# IO.net
KiCad netlist of a schematic drawn in EAGLE
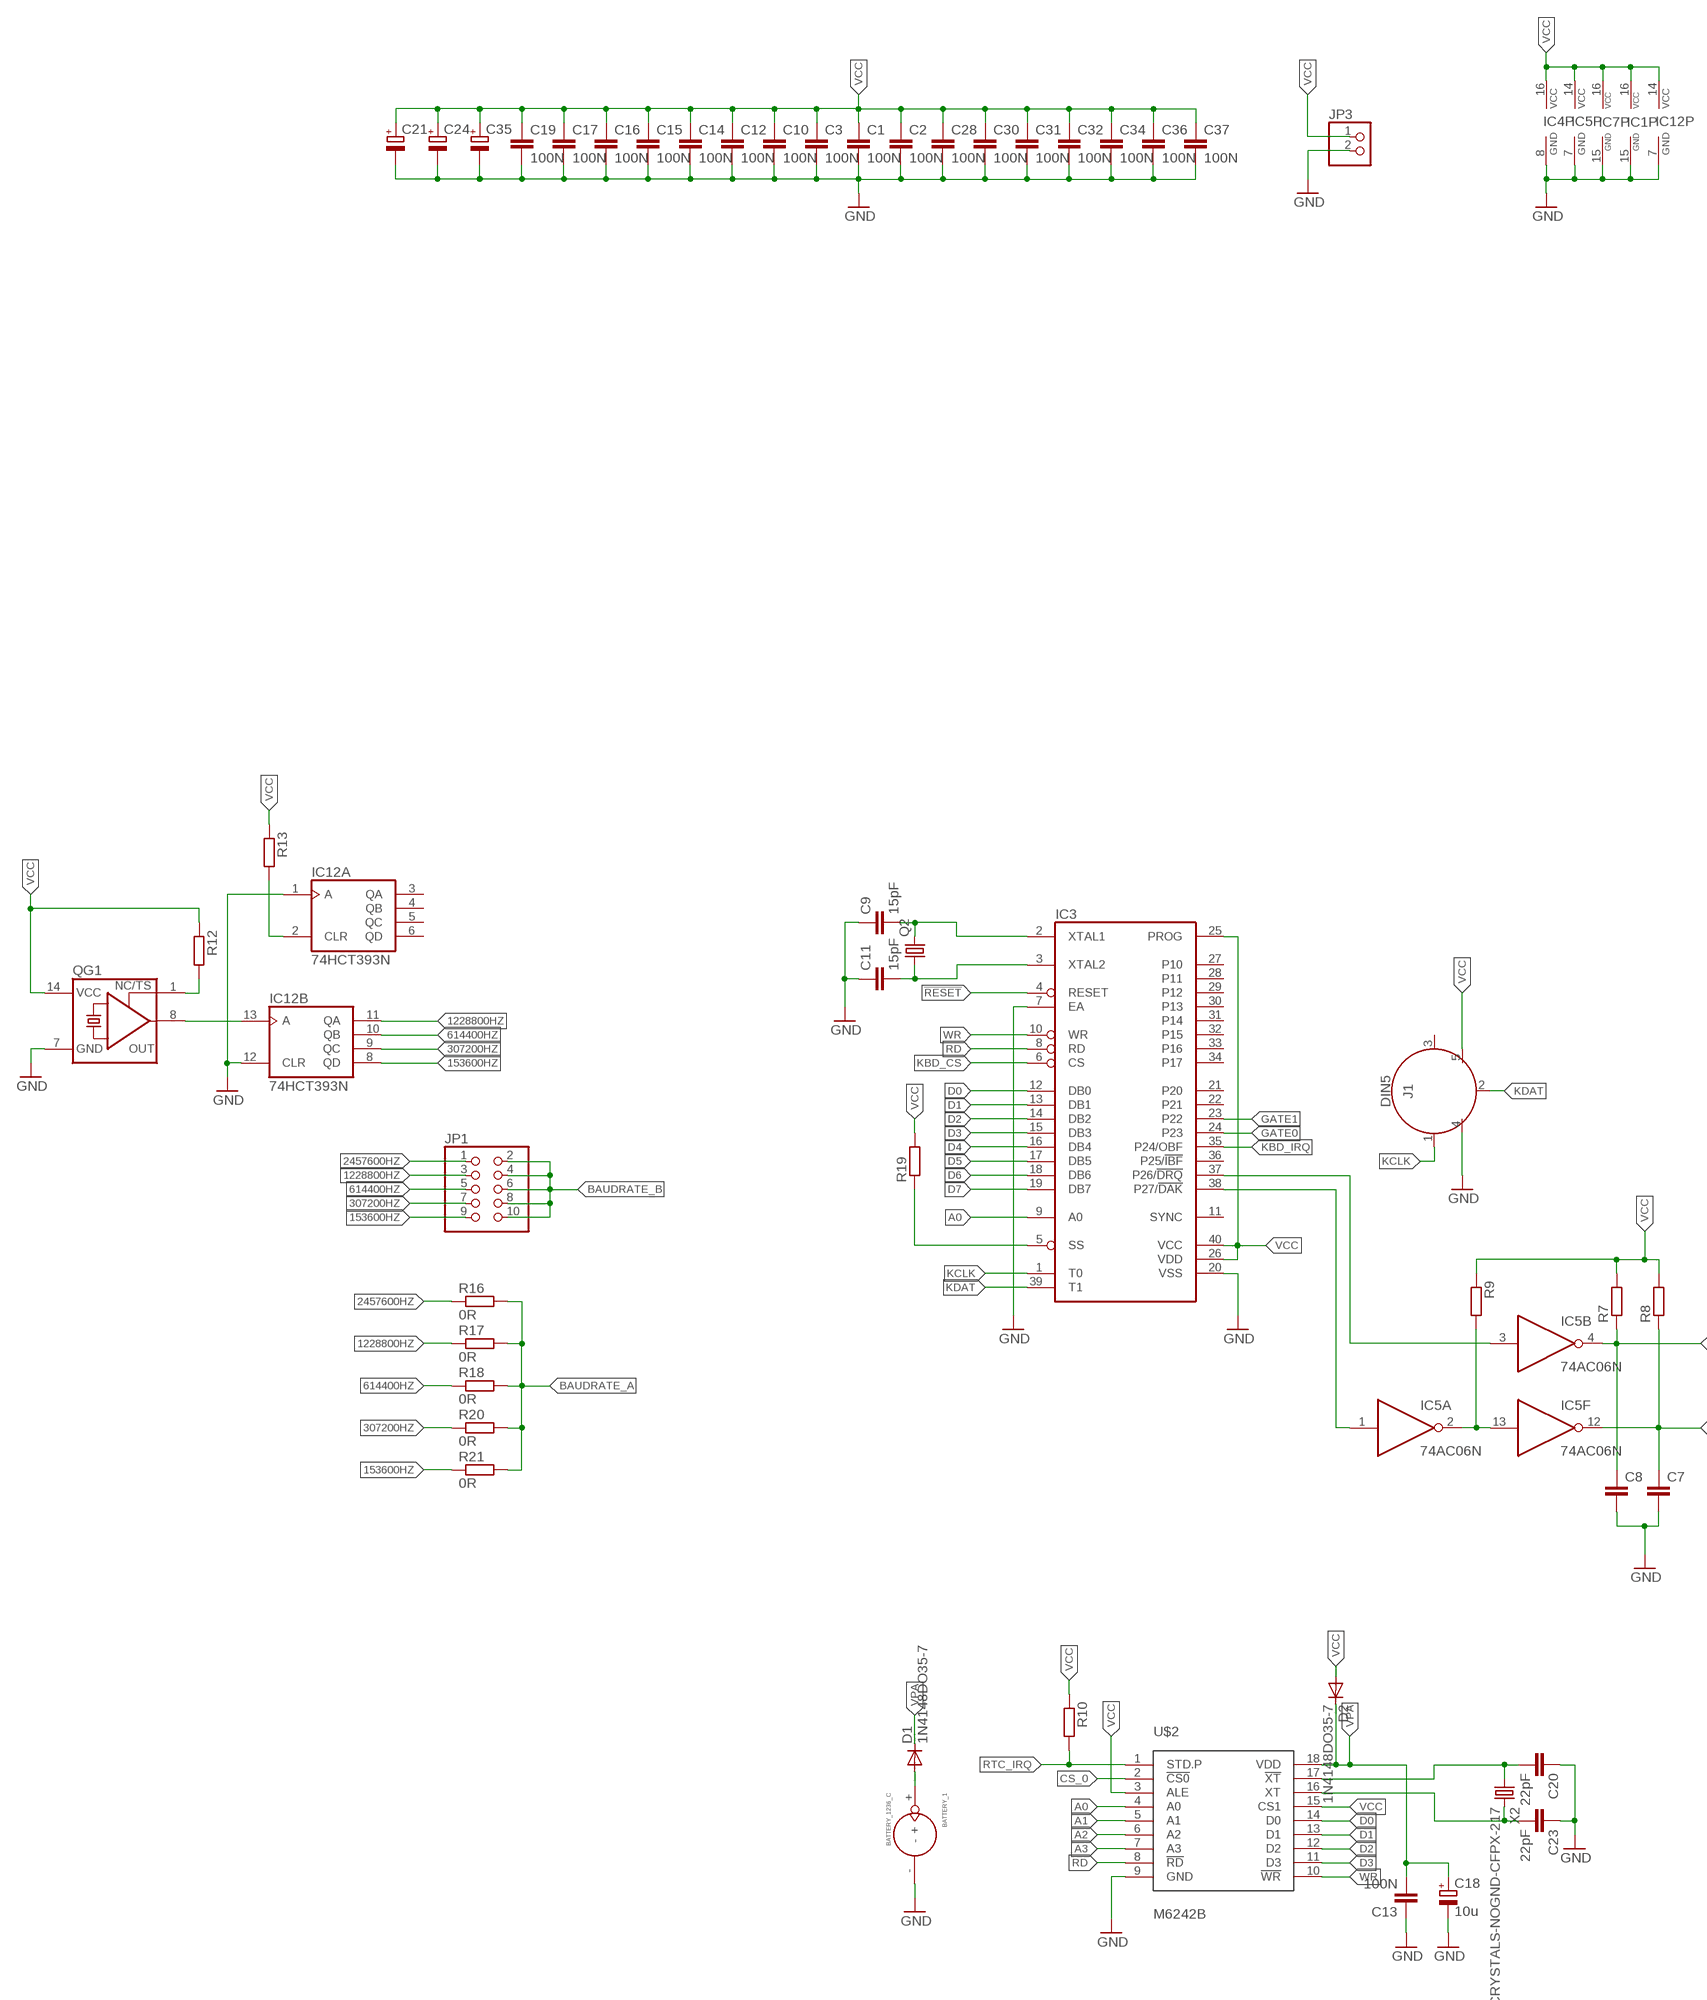
[diagram p0: schematic, sheet 1, part 1 of 3]
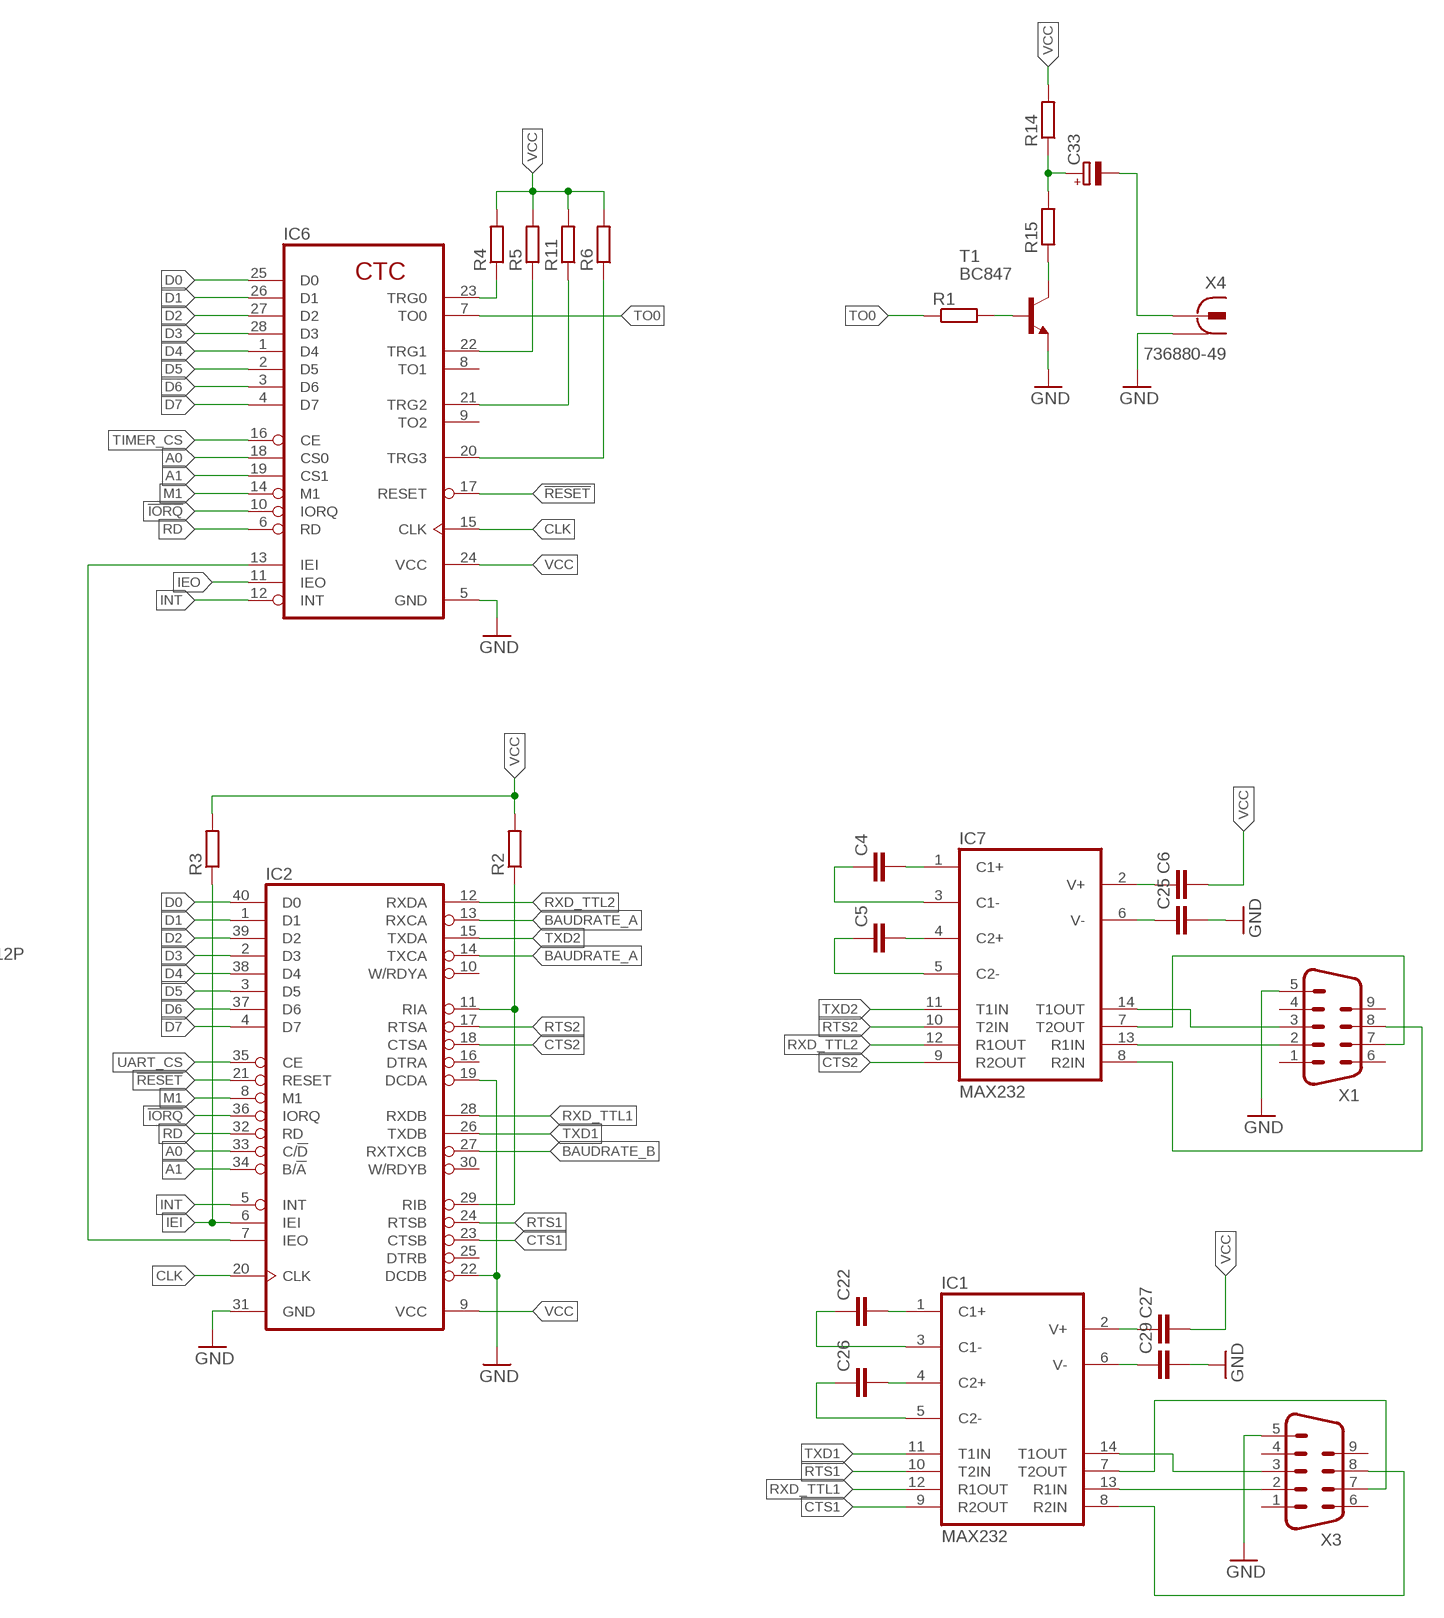
[diagram p1: schematic, sheet 1, part 2 of 3]
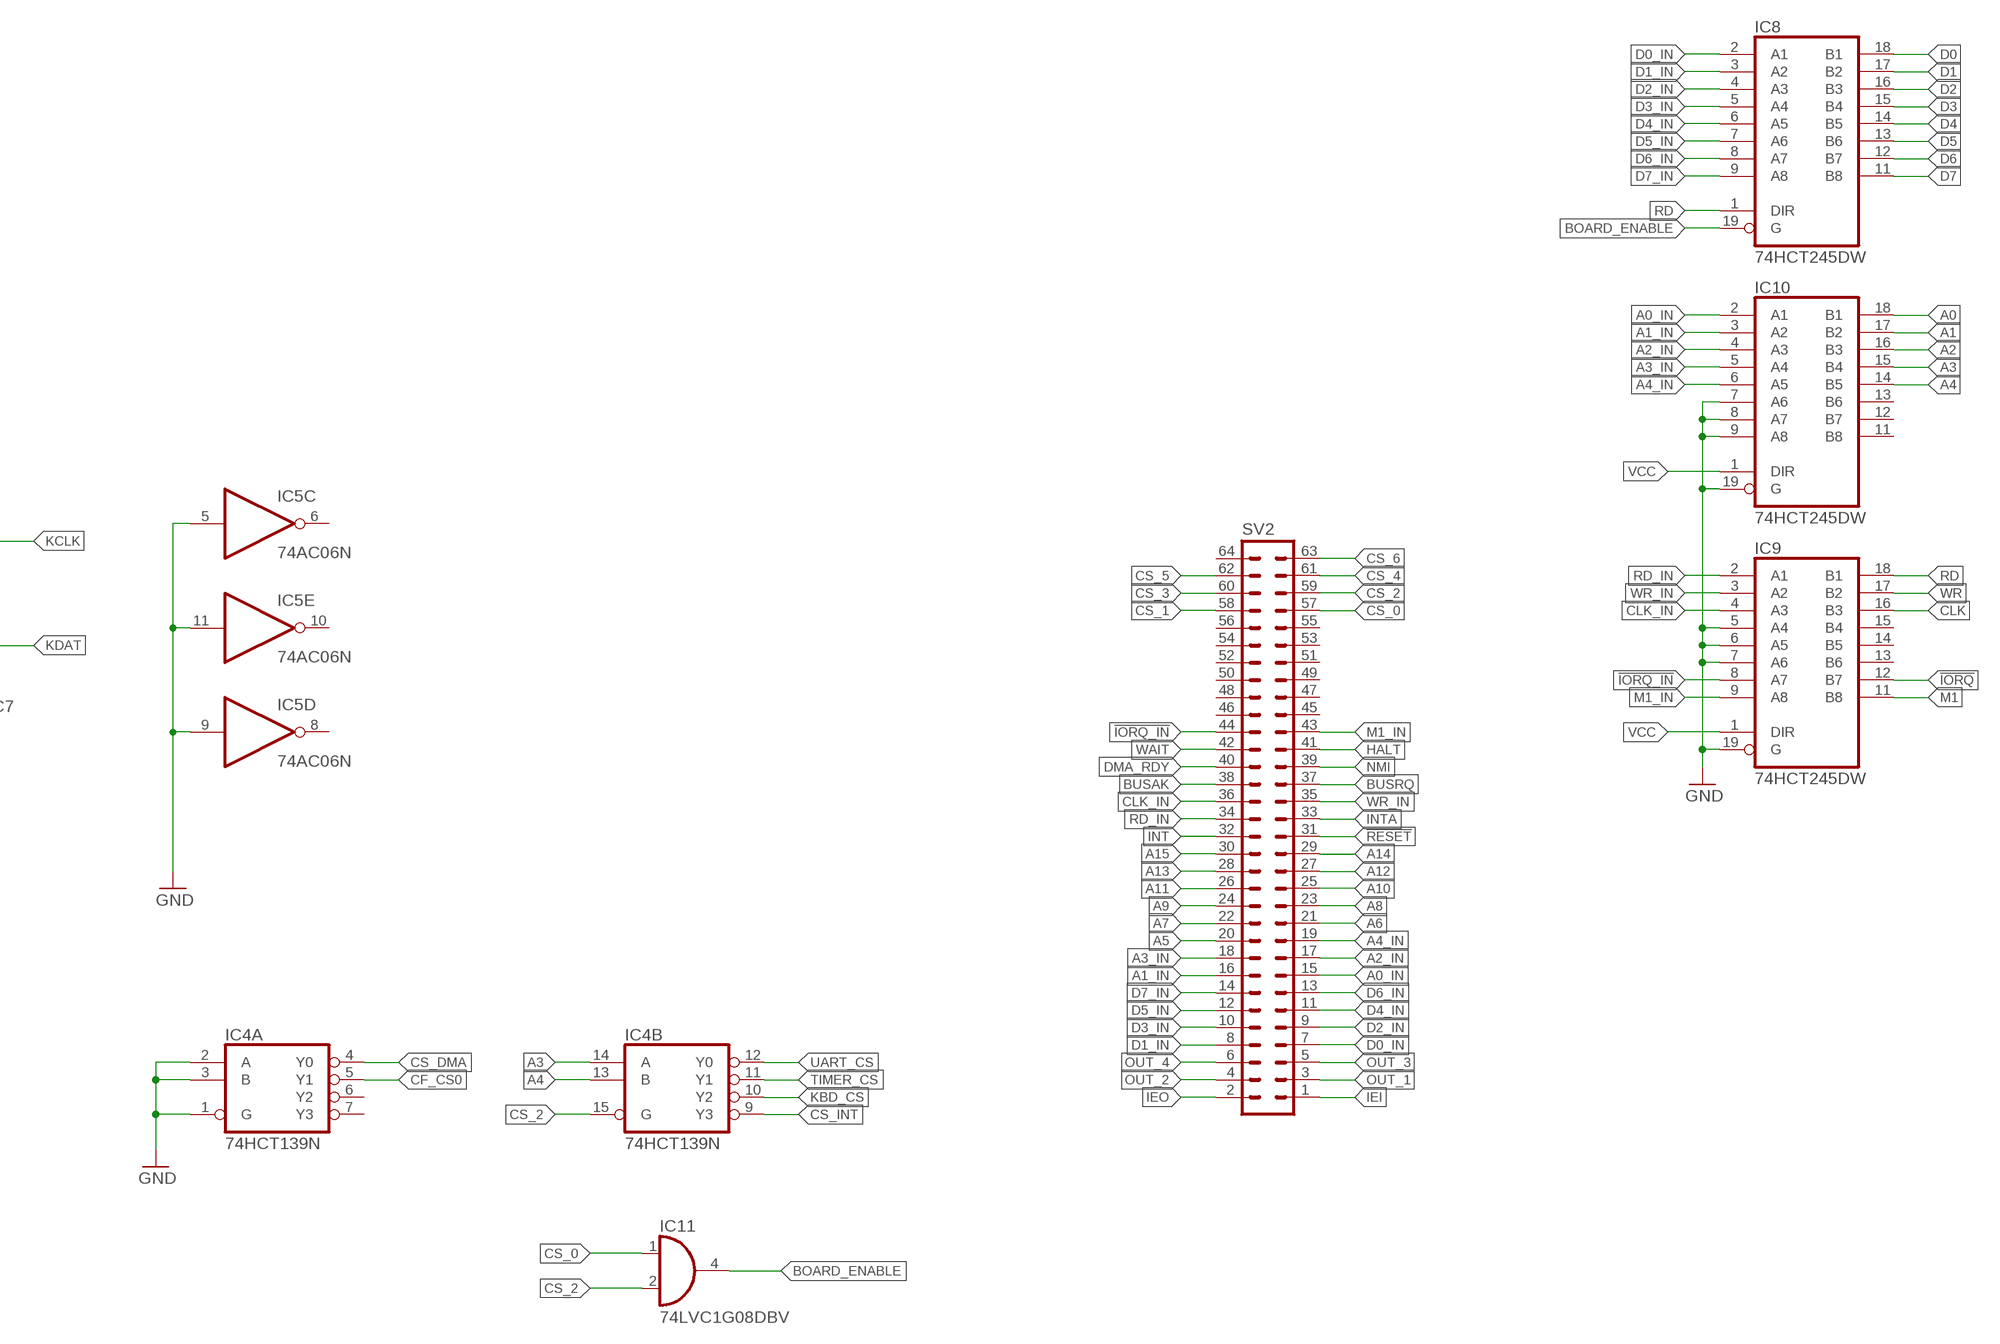
[diagram p2: schematic, sheet 1, part 3 of 3]

(export (version "E")
  (design (tool "Eeschema 10.0.6"))
  (components
    (comp (ref "BATTERY_1")
      (value "BATTERY_1236_C")
      (footprint "eagle-import:BATTERY_1236_C")
      (libsource (lib "eagle-import") (part "BATTERY_1236_C"))
    )
    (comp (ref "C1")
      (value "100N")
      (footprint "eagle-import:C0603")
      (libsource (lib "eagle-import") (part "C-EUC0603"))
    )
    (comp (ref "C2")
      (value "100N")
      (footprint "eagle-import:C1206")
      (libsource (lib "eagle-import") (part "C-EUC1206"))
    )
    (comp (ref "C3")
      (value "100N")
      (footprint "eagle-import:C0603")
      (libsource (lib "eagle-import") (part "C-EUC0603"))
    )
    (comp (ref "C4")
      (value "C-EUC0603")
      (footprint "eagle-import:C0603")
      (libsource (lib "eagle-import") (part "C-EUC0603"))
    )
    (comp (ref "C5")
      (value "C-EUC0603")
      (footprint "eagle-import:C0603")
      (libsource (lib "eagle-import") (part "C-EUC0603"))
    )
    (comp (ref "C6")
      (value "C-EUC0603")
      (footprint "eagle-import:C0603")
      (libsource (lib "eagle-import") (part "C-EUC0603"))
    )
    (comp (ref "C7")
      (value "C-EUC0603")
      (footprint "eagle-import:C0603")
      (libsource (lib "eagle-import") (part "C-EUC0603"))
    )
    (comp (ref "C8")
      (value "C-EUC0603")
      (footprint "eagle-import:C0603")
      (libsource (lib "eagle-import") (part "C-EUC0603"))
    )
    (comp (ref "C9")
      (value "15pF")
      (footprint "eagle-import:C0603")
      (libsource (lib "eagle-import") (part "C-EUC0603"))
    )
    (comp (ref "C10")
      (value "100N")
      (footprint "eagle-import:C0603")
      (libsource (lib "eagle-import") (part "C-EUC0603"))
    )
    (comp (ref "C11")
      (value "15pF")
      (footprint "eagle-import:C0603")
      (libsource (lib "eagle-import") (part "C-EUC0603"))
    )
    (comp (ref "C12")
      (value "100N")
      (footprint "eagle-import:C0603")
      (libsource (lib "eagle-import") (part "C-EUC0603"))
    )
    (comp (ref "C13")
      (value "100N")
      (footprint "eagle-import:C0603")
      (libsource (lib "eagle-import") (part "C-EUC0603"))
    )
    (comp (ref "C14")
      (value "100N")
      (footprint "eagle-import:C0603")
      (libsource (lib "eagle-import") (part "C-EUC0603"))
    )
    (comp (ref "C15")
      (value "100N")
      (footprint "eagle-import:C0603")
      (libsource (lib "eagle-import") (part "C-EUC0603"))
    )
    (comp (ref "C16")
      (value "100N")
      (footprint "eagle-import:C0603")
      (libsource (lib "eagle-import") (part "C-EUC0603"))
    )
    (comp (ref "C17")
      (value "100N")
      (footprint "eagle-import:C0603")
      (libsource (lib "eagle-import") (part "C-EUC0603"))
    )
    (comp (ref "C18")
      (value "10u")
      (footprint "eagle-import:SMC_B")
      (libsource (lib "eagle-import") (part "CPOL-EUSMCB"))
    )
    (comp (ref "C19")
      (value "100N")
      (footprint "eagle-import:C0603")
      (libsource (lib "eagle-import") (part "C-EUC0603"))
    )
    (comp (ref "C20")
      (value "22pF")
      (footprint "eagle-import:C0603")
      (libsource (lib "eagle-import") (part "C-EUC0603"))
    )
    (comp (ref "C21")
      (value "CPOL-EUSMCB")
      (footprint "eagle-import:SMC_B")
      (libsource (lib "eagle-import") (part "CPOL-EUSMCB"))
    )
    (comp (ref "C22")
      (value "C-EUC0603")
      (footprint "eagle-import:C0603")
      (libsource (lib "eagle-import") (part "C-EUC0603"))
    )
    (comp (ref "C23")
      (value "22pF")
      (footprint "eagle-import:C0603")
      (libsource (lib "eagle-import") (part "C-EUC0603"))
    )
    (comp (ref "C24")
      (value "CPOL-EUSMCB")
      (footprint "eagle-import:SMC_B")
      (libsource (lib "eagle-import") (part "CPOL-EUSMCB"))
    )
    (comp (ref "C25")
      (value "C-EUC0603")
      (footprint "eagle-import:C0603")
      (libsource (lib "eagle-import") (part "C-EUC0603"))
    )
    (comp (ref "C26")
      (value "C-EUC0603")
      (footprint "eagle-import:C0603")
      (libsource (lib "eagle-import") (part "C-EUC0603"))
    )
    (comp (ref "C27")
      (value "C-EUC0603")
      (footprint "eagle-import:C0603")
      (libsource (lib "eagle-import") (part "C-EUC0603"))
    )
    (comp (ref "C28")
      (value "100N")
      (footprint "eagle-import:C0603")
      (libsource (lib "eagle-import") (part "C-EUC0603"))
    )
    (comp (ref "C29")
      (value "C-EUC0603")
      (footprint "eagle-import:C0603")
      (libsource (lib "eagle-import") (part "C-EUC0603"))
    )
    (comp (ref "C30")
      (value "100N")
      (footprint "eagle-import:C0603")
      (libsource (lib "eagle-import") (part "C-EUC0603"))
    )
    (comp (ref "C31")
      (value "100N")
      (footprint "eagle-import:C0603")
      (libsource (lib "eagle-import") (part "C-EUC0603"))
    )
    (comp (ref "C32")
      (value "100N")
      (footprint "eagle-import:C0603")
      (libsource (lib "eagle-import") (part "C-EUC0603"))
    )
    (comp (ref "C33")
      (value "CPOL-EUE2-4")
      (footprint "eagle-import:E2-4")
      (libsource (lib "eagle-import") (part "CPOL-EUE2-4"))
    )
    (comp (ref "C34")
      (value "100N")
      (footprint "eagle-import:C0603")
      (libsource (lib "eagle-import") (part "C-EUC0603"))
    )
    (comp (ref "C35")
      (value "CPOL-EUE5-10.5")
      (footprint "eagle-import:E5-10,5")
      (libsource (lib "eagle-import") (part "CPOL-EUE5-10.5"))
    )
    (comp (ref "C36")
      (value "100N")
      (footprint "eagle-import:C0603")
      (libsource (lib "eagle-import") (part "C-EUC0603"))
    )
    (comp (ref "C37")
      (value "100N")
      (footprint "eagle-import:C0603")
      (libsource (lib "eagle-import") (part "C-EUC0603"))
    )
    (comp (ref "D1")
      (value "1N4148DO35-7")
      (footprint "eagle-import:DO35-7")
      (libsource (lib "eagle-import") (part "1N4148DO35-7"))
    )
    (comp (ref "D2")
      (value "1N4148DO35-7")
      (footprint "eagle-import:DO35-7")
      (libsource (lib "eagle-import") (part "1N4148DO35-7"))
    )
    (comp (ref "IC1")
      (value "MAX232")
      (footprint "eagle-import:DIL16")
      (fields (field (name "MF") "MAXIM") (field (name "MPN") "MAX232ACPE+"))
      (libsource (lib "eagle-import") (part "MAX232"))
    )
    (comp (ref "IC2")
      (value "Z80DART")
      (footprint "eagle-import:DIL40")
      (libsource (lib "eagle-import") (part "Z80DART"))
    )
    (comp (ref "IC3")
      (value "UPI-8042AH")
      (footprint "eagle-import:DIL40")
      (libsource (lib "eagle-import") (part "UPI-8042AH"))
    )
    (comp (ref "IC4")
      (value "74HCT139N")
      (footprint "eagle-import:DIL16")
      (libsource (lib "eagle-import") (part "74139NHCT"))
    )
    (comp (ref "IC5")
      (value "74AC06N")
      (footprint "eagle-import:DIL14")
      (libsource (lib "eagle-import") (part "7406NAC"))
    )
    (comp (ref "IC6")
      (value "Z80CTC")
      (footprint "eagle-import:DIL28")
      (libsource (lib "eagle-import") (part "Z80CTC"))
    )
    (comp (ref "IC7")
      (value "MAX232")
      (footprint "eagle-import:DIL16")
      (fields (field (name "MF") "MAXIM") (field (name "MPN") "MAX232ACPE+"))
      (libsource (lib "eagle-import") (part "MAX232"))
    )
    (comp (ref "IC8")
      (value "74HCT245DW")
      (footprint "eagle-import:SO20W")
      (libsource (lib "eagle-import") (part "74245DWHCT"))
    )
    (comp (ref "IC9")
      (value "74HCT245DW")
      (footprint "eagle-import:SO20W")
      (libsource (lib "eagle-import") (part "74245DWHCT"))
    )
    (comp (ref "IC10")
      (value "74HCT245DW")
      (footprint "eagle-import:SO20W")
      (libsource (lib "eagle-import") (part "74245DWHCT"))
    )
    (comp (ref "IC11")
      (value "74LVC1G08DBV")
      (footprint "eagle-import:SOT23-5")
      (libsource (lib "eagle-import") (part "741G08DBVLVC"))
    )
    (comp (ref "IC12")
      (value "74HCT393N")
      (footprint "eagle-import:DIL14")
      (libsource (lib "eagle-import") (part "74393NHCT"))
    )
    (comp (ref "J1")
      (value "DIN5")
      (footprint "eagle-import:DIN5-RA-PTH")
      (libsource (lib "eagle-import") (part "DIN5"))
    )
    (comp (ref "JP1")
      (value "PINHD-2X5")
      (footprint "eagle-import:2X05")
      (libsource (lib "eagle-import") (part "PINHD-2X5"))
    )
    (comp (ref "JP3")
      (value "PINHD-1X2/90")
      (footprint "eagle-import:1X02_90")
      (libsource (lib "eagle-import") (part "PINHD-1X2/90"))
    )
    (comp (ref "Q2")
      (value "CRYSTALHC49S")
      (footprint "eagle-import:HC49_S")
      (libsource (lib "eagle-import") (part "CRYSTALHC49S"))
    )
    (comp (ref "QG1")
      (value "XO-14")
      (footprint "eagle-import:DIL14S")
      (libsource (lib "eagle-import") (part "XO-14"))
    )
    (comp (ref "R1")
      (value "R-EU_R0603")
      (footprint "eagle-import:R0603")
      (libsource (lib "eagle-import") (part "R-EU_R0603"))
    )
    (comp (ref "R2")
      (value "R-EU_R0603")
      (footprint "eagle-import:R0603")
      (libsource (lib "eagle-import") (part "R-EU_R0603"))
    )
    (comp (ref "R3")
      (value "R-EU_0204/5")
      (footprint "eagle-import:0204_5")
      (libsource (lib "eagle-import") (part "R-EU_0204/5"))
    )
    (comp (ref "R4")
      (value "R-EU_R0603")
      (footprint "eagle-import:R0603")
      (libsource (lib "eagle-import") (part "R-EU_R0603"))
    )
    (comp (ref "R5")
      (value "R-EU_R0603")
      (footprint "eagle-import:R0603")
      (libsource (lib "eagle-import") (part "R-EU_R0603"))
    )
    (comp (ref "R6")
      (value "R-EU_0204/5")
      (footprint "eagle-import:0204_5")
      (libsource (lib "eagle-import") (part "R-EU_0204/5"))
    )
    (comp (ref "R7")
      (value "R-EU_0204/7")
      (footprint "eagle-import:0204_7")
      (libsource (lib "eagle-import") (part "R-EU_0204/7"))
    )
    (comp (ref "R8")
      (value "R-EU_M0805")
      (footprint "eagle-import:M0805")
      (libsource (lib "eagle-import") (part "R-EU_M0805"))
    )
    (comp (ref "R9")
      (value "R-EU_R0603")
      (footprint "eagle-import:R0603")
      (libsource (lib "eagle-import") (part "R-EU_R0603"))
    )
    (comp (ref "R10")
      (value "R-EU_R0603")
      (footprint "eagle-import:R0603")
      (libsource (lib "eagle-import") (part "R-EU_R0603"))
    )
    (comp (ref "R11")
      (value "R-EU_R0603")
      (footprint "eagle-import:R0603")
      (libsource (lib "eagle-import") (part "R-EU_R0603"))
    )
    (comp (ref "R12")
      (value "R-EU_R0603")
      (footprint "eagle-import:R0603")
      (libsource (lib "eagle-import") (part "R-EU_R0603"))
    )
    (comp (ref "R13")
      (value "R-EU_R0603")
      (footprint "eagle-import:R0603")
      (libsource (lib "eagle-import") (part "R-EU_R0603"))
    )
    (comp (ref "R14")
      (value "R-EU_0204/7")
      (footprint "eagle-import:0204_7")
      (libsource (lib "eagle-import") (part "R-EU_0204/7"))
    )
    (comp (ref "R15")
      (value "R-EU_R0603")
      (footprint "eagle-import:R0603")
      (libsource (lib "eagle-import") (part "R-EU_R0603"))
    )
    (comp (ref "R16")
      (value "0R")
      (footprint "eagle-import:R0603")
      (libsource (lib "eagle-import") (part "R-EU_R0603"))
    )
    (comp (ref "R17")
      (value "0R")
      (footprint "eagle-import:R0603")
      (libsource (lib "eagle-import") (part "R-EU_R0603"))
    )
    (comp (ref "R18")
      (value "0R")
      (footprint "eagle-import:R0603")
      (libsource (lib "eagle-import") (part "R-EU_R0603"))
    )
    (comp (ref "R19")
      (value "R-EU_0204/5")
      (footprint "eagle-import:0204_5")
      (libsource (lib "eagle-import") (part "R-EU_0204/5"))
    )
    (comp (ref "R20")
      (value "0R")
      (footprint "eagle-import:R0603")
      (libsource (lib "eagle-import") (part "R-EU_R0603"))
    )
    (comp (ref "R21")
      (value "0R")
      (footprint "eagle-import:R0603")
      (libsource (lib "eagle-import") (part "R-EU_R0603"))
    )
    (comp (ref "SV2")
      (value "ML64L")
      (footprint "eagle-import:ML64L")
      (libsource (lib "eagle-import") (part "ML64L"))
    )
    (comp (ref "T1")
      (value "BC847")
      (footprint "eagle-import:SOT23")
      (libsource (lib "eagle-import") (part "BC847"))
    )
    (comp (ref "U$2")
      (value "M6242B")
      (footprint "eagle-import:DIL18")
      (libsource (lib "eagle-import") (part "M6242B"))
    )
    (comp (ref "X1")
      (value "M09HP")
      (footprint "eagle-import:M09HP")
      (libsource (lib "eagle-import") (part "M09HP"))
    )
    (comp (ref "X2")
      (value "CRYSTALS-NOGND-CFPX-217")
      (footprint "eagle-import:3.2X1.5-2-PAD")
      (libsource (lib "eagle-import") (part "CRYSTALS-NOGND-CFPX-217"))
    )
    (comp (ref "X3")
      (value "M09HP")
      (footprint "eagle-import:M09HP")
      (libsource (lib "eagle-import") (part "M09HP"))
    )
    (comp (ref "X4")
      (value "736880-49")
      (footprint "eagle-import:736880-49")
      (libsource (lib "eagle-import") (part "736880-49"))
    )
  )
  (nets
    (net (code "1") (name "/~{IORQ_IN}") (class "Default")
      (node (ref "IC9") (pin "8") (pinfunction "A7_8") (pintype "bidirectional"))
      (node (ref "SV2") (pin "44") (pinfunction "44_44") (pintype "passive"))
    )
    (net (code "2") (name "/~{IORQ}") (class "Default")
      (node (ref "IC2") (pin "36") (pinfunction "IORQ_36") (pintype "input"))
      (node (ref "IC6") (pin "10") (pinfunction "IORQ_10") (pintype "input"))
      (node (ref "IC9") (pin "12") (pinfunction "B7_12") (pintype "bidirectional"))
    )
    (net (code "3") (name "/~{RESET}") (class "Default")
      (node (ref "IC2") (pin "21") (pinfunction "RESET_21") (pintype "input"))
      (node (ref "IC3") (pin "4") (pinfunction "RESET_4") (pintype "input"))
      (node (ref "IC6") (pin "17") (pinfunction "RESET_17") (pintype "input"))
      (node (ref "SV2") (pin "31") (pinfunction "31_31") (pintype "passive"))
    )
    (net (code "4") (name "153600HZ") (class "Default")
      (node (ref "IC12") (pin "8") (pinfunction "QD_8") (pintype "output"))
      (node (ref "JP1") (pin "9") (pinfunction "9_9") (pintype "passive"))
      (node (ref "R21") (pin "1") (pinfunction "1_1") (pintype "passive"))
    )
    (net (code "5") (name "307200HZ") (class "Default")
      (node (ref "IC12") (pin "9") (pinfunction "QC_9") (pintype "output"))
      (node (ref "JP1") (pin "7") (pinfunction "7_7") (pintype "passive"))
      (node (ref "R20") (pin "1") (pinfunction "1_1") (pintype "passive"))
    )
    (net (code "6") (name "614400HZ") (class "Default")
      (node (ref "IC12") (pin "10") (pinfunction "QB_10") (pintype "output"))
      (node (ref "JP1") (pin "5") (pinfunction "5_5") (pintype "passive"))
      (node (ref "R18") (pin "1") (pinfunction "1_1") (pintype "passive"))
    )
    (net (code "7") (name "1228800HZ") (class "Default")
      (node (ref "IC12") (pin "11") (pinfunction "QA_11") (pintype "output"))
      (node (ref "JP1") (pin "3") (pinfunction "3_3") (pintype "passive"))
      (node (ref "R17") (pin "1") (pinfunction "1_1") (pintype "passive"))
    )
    (net (code "8") (name "2457600HZ") (class "Default")
      (node (ref "IC12") (pin "13") (pinfunction "A_13") (pintype "input"))
      (node (ref "JP1") (pin "1") (pinfunction "1_1") (pintype "passive"))
      (node (ref "QG1") (pin "8") (pinfunction "OUT_8") (pintype "output"))
      (node (ref "R16") (pin "1") (pinfunction "1_1") (pintype "passive"))
    )
    (net (code "9") (name "A0") (class "Default")
      (node (ref "IC10") (pin "18") (pinfunction "B1_18") (pintype "bidirectional"))
      (node (ref "IC2") (pin "33") (pinfunction "C/~{D}_33") (pintype "input"))
      (node (ref "IC3") (pin "9") (pinfunction "A0_9") (pintype "input"))
      (node (ref "IC6") (pin "18") (pinfunction "CS0_18") (pintype "input"))
      (node (ref "U$2") (pin "4") (pinfunction "A0_4") (pintype "bidirectional"))
    )
    (net (code "10") (name "A0_IN") (class "Default")
      (node (ref "IC10") (pin "2") (pinfunction "A1_2") (pintype "bidirectional"))
      (node (ref "SV2") (pin "15") (pinfunction "15_15") (pintype "passive"))
    )
    (net (code "11") (name "A1") (class "Default")
      (node (ref "IC10") (pin "17") (pinfunction "B2_17") (pintype "bidirectional"))
      (node (ref "IC2") (pin "34") (pinfunction "B/~{A}_34") (pintype "input"))
      (node (ref "IC6") (pin "19") (pinfunction "CS1_19") (pintype "input"))
      (node (ref "U$2") (pin "5") (pinfunction "A1_5") (pintype "bidirectional"))
    )
    (net (code "12") (name "A1_IN") (class "Default")
      (node (ref "IC10") (pin "3") (pinfunction "A2_3") (pintype "bidirectional"))
      (node (ref "SV2") (pin "16") (pinfunction "16_16") (pintype "passive"))
    )
    (net (code "13") (name "A2") (class "Default")
      (node (ref "IC10") (pin "16") (pinfunction "B3_16") (pintype "bidirectional"))
      (node (ref "U$2") (pin "6") (pinfunction "A2_6") (pintype "bidirectional"))
    )
    (net (code "14") (name "A2_IN") (class "Default")
      (node (ref "IC10") (pin "4") (pinfunction "A3_4") (pintype "bidirectional"))
      (node (ref "SV2") (pin "17") (pinfunction "17_17") (pintype "passive"))
    )
    (net (code "15") (name "A3") (class "Default")
      (node (ref "IC10") (pin "15") (pinfunction "B4_15") (pintype "bidirectional"))
      (node (ref "IC4") (pin "14") (pinfunction "A_14") (pintype "input"))
      (node (ref "U$2") (pin "7") (pinfunction "A3_7") (pintype "bidirectional"))
    )
    (net (code "16") (name "A3_IN") (class "Default")
      (node (ref "IC10") (pin "5") (pinfunction "A4_5") (pintype "bidirectional"))
      (node (ref "SV2") (pin "18") (pinfunction "18_18") (pintype "passive"))
    )
    (net (code "17") (name "A4") (class "Default")
      (node (ref "IC10") (pin "14") (pinfunction "B5_14") (pintype "bidirectional"))
      (node (ref "IC4") (pin "13") (pinfunction "B_13") (pintype "input"))
    )
    (net (code "18") (name "A4_IN") (class "Default")
      (node (ref "IC10") (pin "6") (pinfunction "A5_6") (pintype "bidirectional"))
      (node (ref "SV2") (pin "19") (pinfunction "19_19") (pintype "passive"))
    )
    (net (code "19") (name "A5") (class "Default")
      (node (ref "SV2") (pin "20") (pinfunction "20_20") (pintype "passive"))
    )
    (net (code "20") (name "A6") (class "Default")
      (node (ref "SV2") (pin "21") (pinfunction "21_21") (pintype "passive"))
    )
    (net (code "21") (name "A7") (class "Default")
      (node (ref "SV2") (pin "22") (pinfunction "22_22") (pintype "passive"))
    )
    (net (code "22") (name "A8") (class "Default")
      (node (ref "SV2") (pin "23") (pinfunction "23_23") (pintype "passive"))
    )
    (net (code "23") (name "A9") (class "Default")
      (node (ref "SV2") (pin "24") (pinfunction "24_24") (pintype "passive"))
    )
    (net (code "24") (name "A10") (class "Default")
      (node (ref "SV2") (pin "25") (pinfunction "25_25") (pintype "passive"))
    )
    (net (code "25") (name "A11") (class "Default")
      (node (ref "SV2") (pin "26") (pinfunction "26_26") (pintype "passive"))
    )
    (net (code "26") (name "A12") (class "Default")
      (node (ref "SV2") (pin "27") (pinfunction "27_27") (pintype "passive"))
    )
    (net (code "27") (name "A13") (class "Default")
      (node (ref "SV2") (pin "28") (pinfunction "28_28") (pintype "passive"))
    )
    (net (code "28") (name "A14") (class "Default")
      (node (ref "SV2") (pin "29") (pinfunction "29_29") (pintype "passive"))
    )
    (net (code "29") (name "A15") (class "Default")
      (node (ref "SV2") (pin "30") (pinfunction "30_30") (pintype "passive"))
    )
    (net (code "30") (name "BAUDRATE_A") (class "Default")
      (node (ref "IC2") (pin "13") (pinfunction "RXCA_13") (pintype "input"))
      (node (ref "IC2") (pin "14") (pinfunction "TXCA_14") (pintype "input"))
      (node (ref "R16") (pin "2") (pinfunction "2_2") (pintype "passive"))
      (node (ref "R17") (pin "2") (pinfunction "2_2") (pintype "passive"))
      (node (ref "R18") (pin "2") (pinfunction "2_2") (pintype "passive"))
      (node (ref "R20") (pin "2") (pinfunction "2_2") (pintype "passive"))
      (node (ref "R21") (pin "2") (pinfunction "2_2") (pintype "passive"))
    )
    (net (code "31") (name "BAUDRATE_B") (class "Default")
      (node (ref "IC2") (pin "27") (pinfunction "RXTXCB_27") (pintype "input"))
      (node (ref "JP1") (pin "10") (pinfunction "10_10") (pintype "passive"))
      (node (ref "JP1") (pin "2") (pinfunction "2_2") (pintype "passive"))
      (node (ref "JP1") (pin "4") (pinfunction "4_4") (pintype "passive"))
      (node (ref "JP1") (pin "6") (pinfunction "6_6") (pintype "passive"))
      (node (ref "JP1") (pin "8") (pinfunction "8_8") (pintype "passive"))
    )
    (net (code "32") (name "BOARD_ENABLE") (class "Default")
      (node (ref "IC11") (pin "4") (pinfunction "O_4") (pintype "output"))
      (node (ref "IC8") (pin "19") (pinfunction "G_19") (pintype "input"))
    )
    (net (code "33") (name "BUSAK") (class "Default")
      (node (ref "SV2") (pin "38") (pinfunction "38_38") (pintype "passive"))
    )
    (net (code "34") (name "BUSRQ") (class "Default")
      (node (ref "SV2") (pin "37") (pinfunction "37_37") (pintype "passive"))
    )
    (net (code "35") (name "CF_CS0") (class "Default")
      (node (ref "IC4") (pin "5") (pinfunction "Y1_5") (pintype "output"))
    )
    (net (code "36") (name "CLK") (class "Default")
      (node (ref "IC2") (pin "20") (pinfunction "CLK_20") (pintype "input"))
      (node (ref "IC6") (pin "15") (pinfunction "CLK_15") (pintype "input"))
      (node (ref "IC9") (pin "16") (pinfunction "B3_16") (pintype "bidirectional"))
    )
    (net (code "37") (name "CLK_IN") (class "Default")
      (node (ref "IC9") (pin "4") (pinfunction "A3_4") (pintype "bidirectional"))
      (node (ref "SV2") (pin "36") (pinfunction "36_36") (pintype "passive"))
    )
    (net (code "38") (name "CS_0") (class "Default")
      (node (ref "IC11") (pin "1") (pinfunction "I0_1") (pintype "input"))
      (node (ref "SV2") (pin "57") (pinfunction "57_57") (pintype "passive"))
      (node (ref "U$2") (pin "2") (pinfunction "~{CS0}_2") (pintype "bidirectional"))
    )
    (net (code "39") (name "CS_1") (class "Default")
      (node (ref "SV2") (pin "58") (pinfunction "58_58") (pintype "passive"))
    )
    (net (code "40") (name "CS_2") (class "Default")
      (node (ref "IC11") (pin "2") (pinfunction "I1_2") (pintype "input"))
      (node (ref "IC4") (pin "15") (pinfunction "G_15") (pintype "input"))
      (node (ref "SV2") (pin "59") (pinfunction "59_59") (pintype "passive"))
    )
    (net (code "41") (name "CS_3") (class "Default")
      (node (ref "SV2") (pin "60") (pinfunction "60_60") (pintype "passive"))
    )
    (net (code "42") (name "CS_4") (class "Default")
      (node (ref "SV2") (pin "61") (pinfunction "61_61") (pintype "passive"))
    )
    (net (code "43") (name "CS_5") (class "Default")
      (node (ref "SV2") (pin "62") (pinfunction "62_62") (pintype "passive"))
    )
    (net (code "44") (name "CS_6") (class "Default")
      (node (ref "SV2") (pin "63") (pinfunction "63_63") (pintype "passive"))
    )
    (net (code "45") (name "CS_DMA") (class "Default")
      (node (ref "IC4") (pin "4") (pinfunction "Y0_4") (pintype "output"))
    )
    (net (code "46") (name "CS_INT") (class "Default")
      (node (ref "IC4") (pin "9") (pinfunction "Y3_9") (pintype "output"))
    )
    (net (code "47") (name "CTS1") (class "Default")
      (node (ref "IC1") (pin "9") (pinfunction "R2OUT_9") (pintype "output"))
      (node (ref "IC2") (pin "23") (pinfunction "CTSB_23") (pintype "input"))
    )
    (net (code "48") (name "CTS2") (class "Default")
      (node (ref "IC2") (pin "18") (pinfunction "CTSA_18") (pintype "input"))
      (node (ref "IC7") (pin "9") (pinfunction "R2OUT_9") (pintype "output"))
    )
    (net (code "49") (name "D0") (class "Default")
      (node (ref "IC2") (pin "40") (pinfunction "D0_40") (pintype "bidirectional"))
      (node (ref "IC3") (pin "12") (pinfunction "DB0_12") (pintype "bidirectional"))
      (node (ref "IC6") (pin "25") (pinfunction "D0_25") (pintype "bidirectional"))
      (node (ref "IC8") (pin "18") (pinfunction "B1_18") (pintype "bidirectional"))
      (node (ref "U$2") (pin "14") (pinfunction "D0_14") (pintype "bidirectional"))
    )
    (net (code "50") (name "D0_IN") (class "Default")
      (node (ref "IC8") (pin "2") (pinfunction "A1_2") (pintype "bidirectional"))
      (node (ref "SV2") (pin "7") (pinfunction "7_7") (pintype "passive"))
    )
    (net (code "51") (name "D1") (class "Default")
      (node (ref "IC2") (pin "1") (pinfunction "D1_1") (pintype "bidirectional"))
      (node (ref "IC3") (pin "13") (pinfunction "DB1_13") (pintype "bidirectional"))
      (node (ref "IC6") (pin "26") (pinfunction "D1_26") (pintype "bidirectional"))
      (node (ref "IC8") (pin "17") (pinfunction "B2_17") (pintype "bidirectional"))
      (node (ref "U$2") (pin "13") (pinfunction "D1_13") (pintype "bidirectional"))
    )
    (net (code "52") (name "D1_IN") (class "Default")
      (node (ref "IC8") (pin "3") (pinfunction "A2_3") (pintype "bidirectional"))
      (node (ref "SV2") (pin "8") (pinfunction "8_8") (pintype "passive"))
    )
    (net (code "53") (name "D2") (class "Default")
      (node (ref "IC2") (pin "39") (pinfunction "D2_39") (pintype "bidirectional"))
      (node (ref "IC3") (pin "14") (pinfunction "DB2_14") (pintype "bidirectional"))
      (node (ref "IC6") (pin "27") (pinfunction "D2_27") (pintype "bidirectional"))
      (node (ref "IC8") (pin "16") (pinfunction "B3_16") (pintype "bidirectional"))
      (node (ref "U$2") (pin "12") (pinfunction "D2_12") (pintype "bidirectional"))
    )
    (net (code "54") (name "D2_IN") (class "Default")
      (node (ref "IC8") (pin "4") (pinfunction "A3_4") (pintype "bidirectional"))
      (node (ref "SV2") (pin "9") (pinfunction "9_9") (pintype "passive"))
    )
    (net (code "55") (name "D3") (class "Default")
      (node (ref "IC2") (pin "2") (pinfunction "D3_2") (pintype "bidirectional"))
      (node (ref "IC3") (pin "15") (pinfunction "DB3_15") (pintype "bidirectional"))
      (node (ref "IC6") (pin "28") (pinfunction "D3_28") (pintype "bidirectional"))
      (node (ref "IC8") (pin "15") (pinfunction "B4_15") (pintype "bidirectional"))
      (node (ref "U$2") (pin "11") (pinfunction "D3_11") (pintype "bidirectional"))
    )
    (net (code "56") (name "D3_IN") (class "Default")
      (node (ref "IC8") (pin "5") (pinfunction "A4_5") (pintype "bidirectional"))
      (node (ref "SV2") (pin "10") (pinfunction "10_10") (pintype "passive"))
    )
    (net (code "57") (name "D4") (class "Default")
      (node (ref "IC2") (pin "38") (pinfunction "D4_38") (pintype "bidirectional"))
      (node (ref "IC3") (pin "16") (pinfunction "DB4_16") (pintype "bidirectional"))
      (node (ref "IC6") (pin "1") (pinfunction "D4_1") (pintype "bidirectional"))
      (node (ref "IC8") (pin "14") (pinfunction "B5_14") (pintype "bidirectional"))
    )
    (net (code "58") (name "D4_IN") (class "Default")
      (node (ref "IC8") (pin "6") (pinfunction "A5_6") (pintype "bidirectional"))
      (node (ref "SV2") (pin "11") (pinfunction "11_11") (pintype "passive"))
    )
    (net (code "59") (name "D5") (class "Default")
      (node (ref "IC2") (pin "3") (pinfunction "D5_3") (pintype "bidirectional"))
      (node (ref "IC3") (pin "17") (pinfunction "DB5_17") (pintype "bidirectional"))
      (node (ref "IC6") (pin "2") (pinfunction "D5_2") (pintype "bidirectional"))
      (node (ref "IC8") (pin "13") (pinfunction "B6_13") (pintype "bidirectional"))
    )
    (net (code "60") (name "D5_IN") (class "Default")
      (node (ref "IC8") (pin "7") (pinfunction "A6_7") (pintype "bidirectional"))
      (node (ref "SV2") (pin "12") (pinfunction "12_12") (pintype "passive"))
    )
    (net (code "61") (name "D6") (class "Default")
      (node (ref "IC2") (pin "37") (pinfunction "D6_37") (pintype "bidirectional"))
      (node (ref "IC3") (pin "18") (pinfunction "DB6_18") (pintype "bidirectional"))
      (node (ref "IC6") (pin "3") (pinfunction "D6_3") (pintype "bidirectional"))
      (node (ref "IC8") (pin "12") (pinfunction "B7_12") (pintype "bidirectional"))
    )
    (net (code "62") (name "D6_IN") (class "Default")
      (node (ref "IC8") (pin "8") (pinfunction "A7_8") (pintype "bidirectional"))
      (node (ref "SV2") (pin "13") (pinfunction "13_13") (pintype "passive"))
    )
    (net (code "63") (name "D7") (class "Default")
      (node (ref "IC2") (pin "4") (pinfunction "D7_4") (pintype "bidirectional"))
      (node (ref "IC3") (pin "19") (pinfunction "DB7_19") (pintype "bidirectional"))
      (node (ref "IC6") (pin "4") (pinfunction "D7_4") (pintype "bidirectional"))
      (node (ref "IC8") (pin "11") (pinfunction "B8_11") (pintype "bidirectional"))
    )
    (net (code "64") (name "D7_IN") (class "Default")
      (node (ref "IC8") (pin "9") (pinfunction "A8_9") (pintype "bidirectional"))
      (node (ref "SV2") (pin "14") (pinfunction "14_14") (pintype "passive"))
    )
    (net (code "65") (name "DMA_RDY") (class "Default")
      (node (ref "SV2") (pin "40") (pinfunction "40_40") (pintype "passive"))
    )
    (net (code "66") (name "GATE0") (class "Default")
      (node (ref "IC3") (pin "24") (pinfunction "P23_24") (pintype "bidirectional"))
    )
    (net (code "67") (name "GATE1") (class "Default")
      (node (ref "IC3") (pin "23") (pinfunction "P22_23") (pintype "bidirectional"))
    )
    (net (code "68") (name "GND") (class "Default")
      (node (ref "BATTERY_1") (pin "-") (pinfunction "-_-") (pintype "bidirectional"))
      (node (ref "C1") (pin "2") (pinfunction "2_2") (pintype "passive"))
      (node (ref "C10") (pin "2") (pinfunction "2_2") (pintype "passive"))
      (node (ref "C11") (pin "1") (pinfunction "1_1") (pintype "passive"))
      (node (ref "C12") (pin "2") (pinfunction "2_2") (pintype "passive"))
      (node (ref "C13") (pin "1") (pinfunction "1_1") (pintype "passive"))
      (node (ref "C14") (pin "2") (pinfunction "2_2") (pintype "passive"))
      (node (ref "C15") (pin "2") (pinfunction "2_2") (pintype "passive"))
      (node (ref "C16") (pin "2") (pinfunction "2_2") (pintype "passive"))
      (node (ref "C17") (pin "2") (pinfunction "2_2") (pintype "passive"))
      (node (ref "C18") (pin "-") (pinfunction "-_-") (pintype "passive"))
      (node (ref "C19") (pin "2") (pinfunction "2_2") (pintype "passive"))
      (node (ref "C2") (pin "2") (pinfunction "2_2") (pintype "passive"))
      (node (ref "C20") (pin "1") (pinfunction "1_1") (pintype "passive"))
      (node (ref "C21") (pin "-") (pinfunction "-_-") (pintype "passive"))
      (node (ref "C23") (pin "1") (pinfunction "1_1") (pintype "passive"))
      (node (ref "C24") (pin "-") (pinfunction "-_-") (pintype "passive"))
      (node (ref "C25") (pin "2") (pinfunction "2_2") (pintype "passive"))
      (node (ref "C28") (pin "2") (pinfunction "2_2") (pintype "passive"))
      (node (ref "C29") (pin "2") (pinfunction "2_2") (pintype "passive"))
      (node (ref "C3") (pin "2") (pinfunction "2_2") (pintype "passive"))
      (node (ref "C30") (pin "2") (pinfunction "2_2") (pintype "passive"))
      (node (ref "C31") (pin "2") (pinfunction "2_2") (pintype "passive"))
      (node (ref "C32") (pin "2") (pinfunction "2_2") (pintype "passive"))
      (node (ref "C34") (pin "2") (pinfunction "2_2") (pintype "passive"))
      (node (ref "C35") (pin "-") (pinfunction "-_-") (pintype "passive"))
      (node (ref "C36") (pin "2") (pinfunction "2_2") (pintype "passive"))
      (node (ref "C37") (pin "2") (pinfunction "2_2") (pintype "passive"))
      (node (ref "C7") (pin "2") (pinfunction "2_2") (pintype "passive"))
      (node (ref "C8") (pin "2") (pinfunction "2_2") (pintype "passive"))
      (node (ref "C9") (pin "1") (pinfunction "1_1") (pintype "passive"))
      (node (ref "IC1") (pin "15") (pinfunction "GND_15") (pintype "power_in"))
      (node (ref "IC10") (pin "19") (pinfunction "G_19") (pintype "input"))
      (node (ref "IC10") (pin "7") (pinfunction "A6_7") (pintype "bidirectional"))
      (node (ref "IC10") (pin "8") (pinfunction "A7_8") (pintype "bidirectional"))
      (node (ref "IC10") (pin "9") (pinfunction "A8_9") (pintype "bidirectional"))
      (node (ref "IC12") (pin "1") (pinfunction "A_1") (pintype "input"))
      (node (ref "IC12") (pin "12") (pinfunction "CLR_12") (pintype "input"))
      (node (ref "IC12") (pin "7") (pinfunction "GND_7") (pintype "power_in"))
      (node (ref "IC2") (pin "19") (pinfunction "DCDA_19") (pintype "input"))
      (node (ref "IC2") (pin "22") (pinfunction "DCDB_22") (pintype "input"))
      (node (ref "IC2") (pin "31") (pinfunction "GND_31") (pintype "power_in"))
      (node (ref "IC3") (pin "20") (pinfunction "VSS_20") (pintype "power_in"))
      (node (ref "IC3") (pin "7") (pinfunction "EA_7") (pintype "input"))
      (node (ref "IC4") (pin "1") (pinfunction "G_1") (pintype "input"))
      (node (ref "IC4") (pin "2") (pinfunction "A_2") (pintype "input"))
      (node (ref "IC4") (pin "3") (pinfunction "B_3") (pintype "input"))
      (node (ref "IC4") (pin "8") (pinfunction "GND_8") (pintype "power_in"))
      (node (ref "IC5") (pin "11") (pinfunction "I_11") (pintype "input"))
      (node (ref "IC5") (pin "5") (pinfunction "I_5") (pintype "input"))
      (node (ref "IC5") (pin "7") (pinfunction "GND_7") (pintype "power_in"))
      (node (ref "IC5") (pin "9") (pinfunction "I_9") (pintype "input"))
      (node (ref "IC6") (pin "5") (pinfunction "GND_5") (pintype "power_in"))
      (node (ref "IC7") (pin "15") (pinfunction "GND_15") (pintype "power_in"))
      (node (ref "IC9") (pin "19") (pinfunction "G_19") (pintype "input"))
      (node (ref "IC9") (pin "5") (pinfunction "A4_5") (pintype "bidirectional"))
      (node (ref "IC9") (pin "6") (pinfunction "A5_6") (pintype "bidirectional"))
      (node (ref "IC9") (pin "7") (pinfunction "A6_7") (pintype "bidirectional"))
      (node (ref "J1") (pin "4") (pinfunction "4_4") (pintype "bidirectional"))
      (node (ref "JP3") (pin "2") (pinfunction "2_2") (pintype "passive"))
      (node (ref "QG1") (pin "7") (pinfunction "GND_7") (pintype "power_in"))
      (node (ref "T1") (pin "2") (pinfunction "E_2") (pintype "passive"))
      (node (ref "U$2") (pin "9") (pinfunction "GND_9") (pintype "bidirectional"))
      (node (ref "X1") (pin "5") (pinfunction "5_5") (pintype "passive"))
      (node (ref "X3") (pin "5") (pinfunction "5_5") (pintype "passive"))
      (node (ref "X4") (pin "1") (pinfunction "1_1") (pintype "passive"))
      (node (ref "X4") (pin "1@1") (pinfunction "1_1@1") (pintype "passive"))
      (node (ref "X4") (pin "1@2") (pinfunction "1_1@2") (pintype "passive"))
    )
    (net (code "69") (name "HALT") (class "Default")
      (node (ref "SV2") (pin "41") (pinfunction "41_41") (pintype "passive"))
    )
    (net (code "70") (name "IEI") (class "Default")
      (node (ref "IC2") (pin "6") (pinfunction "IEI_6") (pintype "input"))
      (node (ref "R3") (pin "1") (pinfunction "1_1") (pintype "passive"))
      (node (ref "SV2") (pin "1") (pinfunction "1_1") (pintype "passive"))
    )
    (net (code "71") (name "IEO") (class "Default")
      (node (ref "IC6") (pin "11") (pinfunction "IEO_11") (pintype "output"))
      (node (ref "SV2") (pin "2") (pinfunction "2_2") (pintype "passive"))
    )
    (net (code "72") (name "INT") (class "Default")
      (node (ref "IC2") (pin "5") (pinfunction "INT_5") (pintype "open_collector"))
      (node (ref "IC6") (pin "12") (pinfunction "INT_12") (pintype "output"))
      (node (ref "SV2") (pin "32") (pinfunction "32_32") (pintype "passive"))
    )
    (net (code "73") (name "INTA") (class "Default")
      (node (ref "SV2") (pin "33") (pinfunction "33_33") (pintype "passive"))
    )
    (net (code "74") (name "KBD_CS") (class "Default")
      (node (ref "IC3") (pin "6") (pinfunction "CS_6") (pintype "input"))
      (node (ref "IC4") (pin "10") (pinfunction "Y2_10") (pintype "output"))
    )
    (net (code "75") (name "KBD_IRQ") (class "Default")
      (node (ref "IC3") (pin "35") (pinfunction "P24/OBF_35") (pintype "bidirectional"))
    )
    (net (code "76") (name "KCLK") (class "Default")
      (node (ref "C8") (pin "1") (pinfunction "1_1") (pintype "passive"))
      (node (ref "IC3") (pin "1") (pinfunction "T0_1") (pintype "input"))
      (node (ref "IC5") (pin "4") (pinfunction "O_4") (pintype "open_collector"))
      (node (ref "J1") (pin "1") (pinfunction "1_1") (pintype "bidirectional"))
      (node (ref "R7") (pin "1") (pinfunction "1_1") (pintype "passive"))
    )
    (net (code "77") (name "KDAT") (class "Default")
      (node (ref "C7") (pin "1") (pinfunction "1_1") (pintype "passive"))
      (node (ref "IC3") (pin "39") (pinfunction "T1_39") (pintype "input"))
      (node (ref "IC5") (pin "12") (pinfunction "O_12") (pintype "open_collector"))
      (node (ref "J1") (pin "2") (pinfunction "2_2") (pintype "bidirectional"))
      (node (ref "R8") (pin "1") (pinfunction "1_1") (pintype "passive"))
    )
    (net (code "78") (name "M1") (class "Default")
      (node (ref "IC2") (pin "8") (pinfunction "M1_8") (pintype "input"))
      (node (ref "IC6") (pin "14") (pinfunction "M1_14") (pintype "input"))
      (node (ref "IC9") (pin "11") (pinfunction "B8_11") (pintype "bidirectional"))
    )
    (net (code "79") (name "M1_IN") (class "Default")
      (node (ref "IC9") (pin "9") (pinfunction "A8_9") (pintype "bidirectional"))
      (node (ref "SV2") (pin "43") (pinfunction "43_43") (pintype "passive"))
    )
    (net (code "80") (name "NMI") (class "Default")
      (node (ref "SV2") (pin "39") (pinfunction "39_39") (pintype "passive"))
    )
    (net (code "81") (name "Net-(BATTERY_1-Pad+)") (class "Default")
      (node (ref "BATTERY_1") (pin "+") (pinfunction "+_+") (pintype "bidirectional"))
      (node (ref "D1") (pin "A") (pinfunction "A_A") (pintype "passive"))
    )
    (net (code "82") (name "Net-(C33-Pad+)") (class "Default")
      (node (ref "C33") (pin "+") (pinfunction "+_+") (pintype "passive"))
      (node (ref "R14") (pin "1") (pinfunction "1_1") (pintype "passive"))
      (node (ref "R15") (pin "2") (pinfunction "2_2") (pintype "passive"))
    )
    (net (code "83") (name "Net-(C33-Pad-)") (class "Default")
      (node (ref "C33") (pin "-") (pinfunction "-_-") (pintype "passive"))
      (node (ref "X4") (pin "2") (pinfunction "2_2") (pintype "passive"))
    )
    (net (code "84") (name "Net-(IC1A-C1+)") (class "Default")
      (node (ref "C22") (pin "2") (pinfunction "2_2") (pintype "passive"))
      (node (ref "IC1") (pin "1") (pinfunction "C1+_1") (pintype "bidirectional"))
    )
    (net (code "85") (name "Net-(IC1A-C1-)") (class "Default")
      (node (ref "C22") (pin "1") (pinfunction "1_1") (pintype "passive"))
      (node (ref "IC1") (pin "3") (pinfunction "C1-_3") (pintype "bidirectional"))
    )
    (net (code "86") (name "Net-(IC1A-C2+)") (class "Default")
      (node (ref "C26") (pin "2") (pinfunction "2_2") (pintype "passive"))
      (node (ref "IC1") (pin "4") (pinfunction "C2+_4") (pintype "bidirectional"))
    )
    (net (code "87") (name "Net-(IC1A-C2-)") (class "Default")
      (node (ref "C26") (pin "1") (pinfunction "1_1") (pintype "passive"))
      (node (ref "IC1") (pin "5") (pinfunction "C2-_5") (pintype "bidirectional"))
    )
    (net (code "88") (name "Net-(IC1A-R1IN)") (class "Default")
      (node (ref "IC1") (pin "13") (pinfunction "R1IN_13") (pintype "input"))
      (node (ref "X3") (pin "2") (pinfunction "2_2") (pintype "passive"))
    )
    (net (code "89") (name "Net-(IC1A-R2IN)") (class "Default")
      (node (ref "IC1") (pin "8") (pinfunction "R2IN_8") (pintype "input"))
      (node (ref "X3") (pin "8") (pinfunction "8_8") (pintype "passive"))
    )
    (net (code "90") (name "Net-(IC1A-T1OUT)") (class "Default")
      (node (ref "IC1") (pin "14") (pinfunction "T1OUT_14") (pintype "output"))
      (node (ref "X3") (pin "3") (pinfunction "3_3") (pintype "passive"))
    )
    (net (code "91") (name "Net-(IC1A-T2OUT)") (class "Default")
      (node (ref "IC1") (pin "7") (pinfunction "T2OUT_7") (pintype "output"))
      (node (ref "X3") (pin "7") (pinfunction "7_7") (pintype "passive"))
    )
    (net (code "92") (name "Net-(IC1A-V+)") (class "Default")
      (node (ref "C27") (pin "1") (pinfunction "1_1") (pintype "passive"))
      (node (ref "IC1") (pin "2") (pinfunction "V+_2") (pintype "bidirectional"))
    )
    (net (code "93") (name "Net-(IC1A-V-)") (class "Default")
      (node (ref "C29") (pin "1") (pinfunction "1_1") (pintype "passive"))
      (node (ref "IC1") (pin "6") (pinfunction "V-_6") (pintype "bidirectional"))
    )
    (net (code "94") (name "Net-(IC2-IEO)") (class "Default")
      (node (ref "IC2") (pin "7") (pinfunction "IEO_7") (pintype "output"))
      (node (ref "IC6") (pin "13") (pinfunction "IEI_13") (pintype "input"))
    )
    (net (code "95") (name "Net-(IC2-RIA)") (class "Default")
      (node (ref "IC2") (pin "11") (pinfunction "RIA_11") (pintype "input"))
      (node (ref "IC2") (pin "29") (pinfunction "RIB_29") (pintype "input"))
      (node (ref "R2") (pin "1") (pinfunction "1_1") (pintype "passive"))
    )
    (net (code "96") (name "Net-(IC3-P26{slash}~{DRQ})") (class "Default")
      (node (ref "IC3") (pin "37") (pinfunction "P26/~{DRQ}_37") (pintype "bidirectional"))
      (node (ref "IC5") (pin "3") (pinfunction "I_3") (pintype "input"))
    )
    (net (code "97") (name "Net-(IC3-P27{slash}~{DAK})") (class "Default")
      (node (ref "IC3") (pin "38") (pinfunction "P27/~{DAK}_38") (pintype "bidirectional"))
      (node (ref "IC5") (pin "1") (pinfunction "I_1") (pintype "input"))
    )
    (net (code "98") (name "Net-(IC3-SS)") (class "Default")
      (node (ref "IC3") (pin "5") (pinfunction "SS_5") (pintype "input"))
      (node (ref "R19") (pin "1") (pinfunction "1_1") (pintype "passive"))
    )
    (net (code "99") (name "Net-(IC3-XTAL1)") (class "Default")
      (node (ref "C9") (pin "2") (pinfunction "2_2") (pintype "passive"))
      (node (ref "IC3") (pin "2") (pinfunction "XTAL1_2") (pintype "input"))
      (node (ref "Q2") (pin "2") (pinfunction "2_2") (pintype "passive"))
    )
    (net (code "100") (name "Net-(IC3-XTAL2)") (class "Default")
      (node (ref "C11") (pin "2") (pinfunction "2_2") (pintype "passive"))
      (node (ref "IC3") (pin "3") (pinfunction "XTAL2_3") (pintype "input"))
      (node (ref "Q2") (pin "1") (pinfunction "1_1") (pintype "passive"))
    )
    (net (code "101") (name "Net-(IC5A-O)") (class "Default")
      (node (ref "IC5") (pin "13") (pinfunction "I_13") (pintype "input"))
      (node (ref "IC5") (pin "2") (pinfunction "O_2") (pintype "open_collector"))
      (node (ref "R9") (pin "2") (pinfunction "2_2") (pintype "passive"))
    )
    (net (code "102") (name "Net-(IC6-TRG0)") (class "Default")
      (node (ref "IC6") (pin "23") (pinfunction "TRG0_23") (pintype "input"))
      (node (ref "R4") (pin "1") (pinfunction "1_1") (pintype "passive"))
    )
    (net (code "103") (name "Net-(IC6-TRG1)") (class "Default")
      (node (ref "IC6") (pin "22") (pinfunction "TRG1_22") (pintype "input"))
      (node (ref "R5") (pin "1") (pinfunction "1_1") (pintype "passive"))
    )
    (net (code "104") (name "Net-(IC6-TRG2)") (class "Default")
      (node (ref "IC6") (pin "21") (pinfunction "TRG2_21") (pintype "input"))
      (node (ref "R11") (pin "1") (pinfunction "1_1") (pintype "passive"))
    )
    (net (code "105") (name "Net-(IC6-TRG3)") (class "Default")
      (node (ref "IC6") (pin "20") (pinfunction "TRG3_20") (pintype "input"))
      (node (ref "R6") (pin "1") (pinfunction "1_1") (pintype "passive"))
    )
    (net (code "106") (name "Net-(IC7A-C1+)") (class "Default")
      (node (ref "C4") (pin "2") (pinfunction "2_2") (pintype "passive"))
      (node (ref "IC7") (pin "1") (pinfunction "C1+_1") (pintype "bidirectional"))
    )
    (net (code "107") (name "Net-(IC7A-C1-)") (class "Default")
      (node (ref "C4") (pin "1") (pinfunction "1_1") (pintype "passive"))
      (node (ref "IC7") (pin "3") (pinfunction "C1-_3") (pintype "bidirectional"))
    )
    (net (code "108") (name "Net-(IC7A-C2+)") (class "Default")
      (node (ref "C5") (pin "2") (pinfunction "2_2") (pintype "passive"))
      (node (ref "IC7") (pin "4") (pinfunction "C2+_4") (pintype "bidirectional"))
    )
    (net (code "109") (name "Net-(IC7A-C2-)") (class "Default")
      (node (ref "C5") (pin "1") (pinfunction "1_1") (pintype "passive"))
      (node (ref "IC7") (pin "5") (pinfunction "C2-_5") (pintype "bidirectional"))
    )
    (net (code "110") (name "Net-(IC7A-R1IN)") (class "Default")
      (node (ref "IC7") (pin "13") (pinfunction "R1IN_13") (pintype "input"))
      (node (ref "X1") (pin "2") (pinfunction "2_2") (pintype "passive"))
    )
    (net (code "111") (name "Net-(IC7A-R2IN)") (class "Default")
      (node (ref "IC7") (pin "8") (pinfunction "R2IN_8") (pintype "input"))
      (node (ref "X1") (pin "8") (pinfunction "8_8") (pintype "passive"))
    )
    (net (code "112") (name "Net-(IC7A-T1OUT)") (class "Default")
      (node (ref "IC7") (pin "14") (pinfunction "T1OUT_14") (pintype "output"))
      (node (ref "X1") (pin "3") (pinfunction "3_3") (pintype "passive"))
    )
    (net (code "113") (name "Net-(IC7A-T2OUT)") (class "Default")
      (node (ref "IC7") (pin "7") (pinfunction "T2OUT_7") (pintype "output"))
      (node (ref "X1") (pin "7") (pinfunction "7_7") (pintype "passive"))
    )
    (net (code "114") (name "Net-(IC7A-V+)") (class "Default")
      (node (ref "C6") (pin "1") (pinfunction "1_1") (pintype "passive"))
      (node (ref "IC7") (pin "2") (pinfunction "V+_2") (pintype "bidirectional"))
    )
    (net (code "115") (name "Net-(IC7A-V-)") (class "Default")
      (node (ref "C25") (pin "1") (pinfunction "1_1") (pintype "passive"))
      (node (ref "IC7") (pin "6") (pinfunction "V-_6") (pintype "bidirectional"))
    )
    (net (code "116") (name "Net-(IC12A-CLR)") (class "Default")
      (node (ref "IC12") (pin "2") (pinfunction "CLR_2") (pintype "input"))
      (node (ref "R13") (pin "2") (pinfunction "2_2") (pintype "passive"))
    )
    (net (code "117") (name "Net-(QG1-TS)") (class "Default")
      (node (ref "QG1") (pin "1") (pinfunction "TS_1") (pintype "passive"))
      (node (ref "R12") (pin "2") (pinfunction "2_2") (pintype "passive"))
    )
    (net (code "118") (name "Net-(T1-B)") (class "Default")
      (node (ref "R1") (pin "2") (pinfunction "2_2") (pintype "passive"))
      (node (ref "T1") (pin "1") (pinfunction "B_1") (pintype "passive"))
    )
    (net (code "119") (name "Net-(T1-C)") (class "Default")
      (node (ref "R15") (pin "1") (pinfunction "1_1") (pintype "passive"))
      (node (ref "T1") (pin "3") (pinfunction "C_3") (pintype "passive"))
    )
    (net (code "120") (name "Net-(U$2-XT)") (class "Default")
      (node (ref "C23") (pin "2") (pinfunction "2_2") (pintype "passive"))
      (node (ref "U$2") (pin "16") (pinfunction "XT_16") (pintype "bidirectional"))
      (node (ref "X2") (pin "2") (pinfunction "2_2") (pintype "passive"))
    )
    (net (code "121") (name "Net-(U$2-~{XT})") (class "Default")
      (node (ref "C20") (pin "2") (pinfunction "2_2") (pintype "passive"))
      (node (ref "U$2") (pin "17") (pinfunction "~{XT}_17") (pintype "bidirectional"))
      (node (ref "X2") (pin "1") (pinfunction "1_1") (pintype "passive"))
    )
    (net (code "122") (name "OUT_1") (class "Default")
      (node (ref "SV2") (pin "3") (pinfunction "3_3") (pintype "passive"))
    )
    (net (code "123") (name "OUT_2") (class "Default")
      (node (ref "SV2") (pin "4") (pinfunction "4_4") (pintype "passive"))
    )
    (net (code "124") (name "OUT_3") (class "Default")
      (node (ref "SV2") (pin "5") (pinfunction "5_5") (pintype "passive"))
    )
    (net (code "125") (name "OUT_4") (class "Default")
      (node (ref "SV2") (pin "6") (pinfunction "6_6") (pintype "passive"))
    )
    (net (code "126") (name "RD") (class "Default")
      (node (ref "IC2") (pin "32") (pinfunction "RD_32") (pintype "input"))
      (node (ref "IC3") (pin "8") (pinfunction "RD_8") (pintype "input"))
      (node (ref "IC6") (pin "6") (pinfunction "RD_6") (pintype "input"))
      (node (ref "IC8") (pin "1") (pinfunction "DIR_1") (pintype "input"))
      (node (ref "IC9") (pin "18") (pinfunction "B1_18") (pintype "bidirectional"))
      (node (ref "U$2") (pin "8") (pinfunction "~{RD}_8") (pintype "bidirectional"))
    )
    (net (code "127") (name "RD_IN") (class "Default")
      (node (ref "IC9") (pin "2") (pinfunction "A1_2") (pintype "bidirectional"))
      (node (ref "SV2") (pin "34") (pinfunction "34_34") (pintype "passive"))
    )
    (net (code "128") (name "RTC_IRQ") (class "Default")
      (node (ref "R10") (pin "2") (pinfunction "2_2") (pintype "passive"))
      (node (ref "U$2") (pin "1") (pinfunction "STD.P_1") (pintype "bidirectional"))
    )
    (net (code "129") (name "RTS1") (class "Default")
      (node (ref "IC1") (pin "10") (pinfunction "T2IN_10") (pintype "input"))
      (node (ref "IC2") (pin "24") (pinfunction "RTSB_24") (pintype "output"))
    )
    (net (code "130") (name "RTS2") (class "Default")
      (node (ref "IC2") (pin "17") (pinfunction "RTSA_17") (pintype "output"))
      (node (ref "IC7") (pin "10") (pinfunction "T2IN_10") (pintype "input"))
    )
    (net (code "131") (name "RXD_TTL1") (class "Default")
      (node (ref "IC1") (pin "12") (pinfunction "R1OUT_12") (pintype "output"))
      (node (ref "IC2") (pin "28") (pinfunction "RXDB_28") (pintype "input"))
    )
    (net (code "132") (name "RXD_TTL2") (class "Default")
      (node (ref "IC2") (pin "12") (pinfunction "RXDA_12") (pintype "input"))
      (node (ref "IC7") (pin "12") (pinfunction "R1OUT_12") (pintype "output"))
    )
    (net (code "133") (name "TIMER_CS") (class "Default")
      (node (ref "IC4") (pin "11") (pinfunction "Y1_11") (pintype "output"))
      (node (ref "IC6") (pin "16") (pinfunction "CE_16") (pintype "input"))
    )
    (net (code "134") (name "TO0") (class "Default")
      (node (ref "IC6") (pin "7") (pinfunction "TO0_7") (pintype "output"))
      (node (ref "R1") (pin "1") (pinfunction "1_1") (pintype "passive"))
    )
    (net (code "135") (name "TXD1") (class "Default")
      (node (ref "IC1") (pin "11") (pinfunction "T1IN_11") (pintype "input"))
      (node (ref "IC2") (pin "26") (pinfunction "TXDB_26") (pintype "output"))
    )
    (net (code "136") (name "TXD2") (class "Default")
      (node (ref "IC2") (pin "15") (pinfunction "TXDA_15") (pintype "output"))
      (node (ref "IC7") (pin "11") (pinfunction "T1IN_11") (pintype "input"))
    )
    (net (code "137") (name "UART_CS") (class "Default")
      (node (ref "IC2") (pin "35") (pinfunction "CE_35") (pintype "input"))
      (node (ref "IC4") (pin "12") (pinfunction "Y0_12") (pintype "output"))
    )
    (net (code "138") (name "VCC") (class "Default")
      (node (ref "C1") (pin "1") (pinfunction "1_1") (pintype "passive"))
      (node (ref "C10") (pin "1") (pinfunction "1_1") (pintype "passive"))
      (node (ref "C12") (pin "1") (pinfunction "1_1") (pintype "passive"))
      (node (ref "C14") (pin "1") (pinfunction "1_1") (pintype "passive"))
      (node (ref "C15") (pin "1") (pinfunction "1_1") (pintype "passive"))
      (node (ref "C16") (pin "1") (pinfunction "1_1") (pintype "passive"))
      (node (ref "C17") (pin "1") (pinfunction "1_1") (pintype "passive"))
      (node (ref "C19") (pin "1") (pinfunction "1_1") (pintype "passive"))
      (node (ref "C2") (pin "1") (pinfunction "1_1") (pintype "passive"))
      (node (ref "C21") (pin "+") (pinfunction "+_+") (pintype "passive"))
      (node (ref "C24") (pin "+") (pinfunction "+_+") (pintype "passive"))
      (node (ref "C27") (pin "2") (pinfunction "2_2") (pintype "passive"))
      (node (ref "C28") (pin "1") (pinfunction "1_1") (pintype "passive"))
      (node (ref "C3") (pin "1") (pinfunction "1_1") (pintype "passive"))
      (node (ref "C30") (pin "1") (pinfunction "1_1") (pintype "passive"))
      (node (ref "C31") (pin "1") (pinfunction "1_1") (pintype "passive"))
      (node (ref "C32") (pin "1") (pinfunction "1_1") (pintype "passive"))
      (node (ref "C34") (pin "1") (pinfunction "1_1") (pintype "passive"))
      (node (ref "C35") (pin "+") (pinfunction "+_+") (pintype "passive"))
      (node (ref "C36") (pin "1") (pinfunction "1_1") (pintype "passive"))
      (node (ref "C37") (pin "1") (pinfunction "1_1") (pintype "passive"))
      (node (ref "C6") (pin "2") (pinfunction "2_2") (pintype "passive"))
      (node (ref "D2") (pin "A") (pinfunction "A_A") (pintype "passive"))
      (node (ref "IC1") (pin "16") (pinfunction "VCC_16") (pintype "power_in"))
      (node (ref "IC10") (pin "1") (pinfunction "DIR_1") (pintype "input"))
      (node (ref "IC12") (pin "14") (pinfunction "VCC_14") (pintype "power_in"))
      (node (ref "IC2") (pin "9") (pinfunction "VCC_9") (pintype "power_in"))
      (node (ref "IC3") (pin "25") (pinfunction "PROG_25") (pintype "bidirectional"))
      (node (ref "IC3") (pin "26") (pinfunction "VDD_26") (pintype "power_in"))
      (node (ref "IC3") (pin "40") (pinfunction "VCC_40") (pintype "power_in"))
      (node (ref "IC4") (pin "16") (pinfunction "VCC_16") (pintype "power_in"))
      (node (ref "IC5") (pin "14") (pinfunction "VCC_14") (pintype "power_in"))
      (node (ref "IC6") (pin "24") (pinfunction "VCC_24") (pintype "power_in"))
      (node (ref "IC7") (pin "16") (pinfunction "VCC_16") (pintype "power_in"))
      (node (ref "IC9") (pin "1") (pinfunction "DIR_1") (pintype "input"))
      (node (ref "J1") (pin "5") (pinfunction "5_5") (pintype "bidirectional"))
      (node (ref "JP3") (pin "1") (pinfunction "1_1") (pintype "passive"))
      (node (ref "QG1") (pin "14") (pinfunction "VCC_14") (pintype "power_in"))
      (node (ref "R10") (pin "1") (pinfunction "1_1") (pintype "passive"))
      (node (ref "R11") (pin "2") (pinfunction "2_2") (pintype "passive"))
      (node (ref "R12") (pin "1") (pinfunction "1_1") (pintype "passive"))
      (node (ref "R13") (pin "1") (pinfunction "1_1") (pintype "passive"))
      (node (ref "R14") (pin "2") (pinfunction "2_2") (pintype "passive"))
      (node (ref "R19") (pin "2") (pinfunction "2_2") (pintype "passive"))
      (node (ref "R2") (pin "2") (pinfunction "2_2") (pintype "passive"))
      (node (ref "R3") (pin "2") (pinfunction "2_2") (pintype "passive"))
      (node (ref "R4") (pin "2") (pinfunction "2_2") (pintype "passive"))
      (node (ref "R5") (pin "2") (pinfunction "2_2") (pintype "passive"))
      (node (ref "R6") (pin "2") (pinfunction "2_2") (pintype "passive"))
      (node (ref "R7") (pin "2") (pinfunction "2_2") (pintype "passive"))
      (node (ref "R8") (pin "2") (pinfunction "2_2") (pintype "passive"))
      (node (ref "R9") (pin "1") (pinfunction "1_1") (pintype "passive"))
      (node (ref "U$2") (pin "15") (pinfunction "CS1_15") (pintype "bidirectional"))
      (node (ref "U$2") (pin "3") (pinfunction "ALE_3") (pintype "bidirectional"))
    )
    (net (code "139") (name "VPA") (class "Default")
      (node (ref "C13") (pin "2") (pinfunction "2_2") (pintype "passive"))
      (node (ref "C18") (pin "+") (pinfunction "+_+") (pintype "passive"))
      (node (ref "D1") (pin "C") (pinfunction "C_C") (pintype "passive"))
      (node (ref "D2") (pin "C") (pinfunction "C_C") (pintype "passive"))
      (node (ref "U$2") (pin "18") (pinfunction "VDD_18") (pintype "bidirectional"))
    )
    (net (code "140") (name "WAIT") (class "Default")
      (node (ref "SV2") (pin "42") (pinfunction "42_42") (pintype "passive"))
    )
    (net (code "141") (name "WR") (class "Default")
      (node (ref "IC3") (pin "10") (pinfunction "WR_10") (pintype "input"))
      (node (ref "IC9") (pin "17") (pinfunction "B2_17") (pintype "bidirectional"))
      (node (ref "U$2") (pin "10") (pinfunction "~{WR}_10") (pintype "bidirectional"))
    )
    (net (code "142") (name "WR_IN") (class "Default")
      (node (ref "IC9") (pin "3") (pinfunction "A2_3") (pintype "bidirectional"))
      (node (ref "SV2") (pin "35") (pinfunction "35_35") (pintype "passive"))
    )
    (net (code "143") (name "unconnected-(IC2-DTRA-Pad16)") (class "Default")
      (node (ref "IC2") (pin "16") (pinfunction "DTRA_16") (pintype "output"))
    )
    (net (code "144") (name "unconnected-(IC2-DTRB-Pad25)") (class "Default")
      (node (ref "IC2") (pin "25") (pinfunction "DTRB_25") (pintype "output"))
    )
    (net (code "145") (name "unconnected-(IC2-W{slash}RDYA-Pad10)") (class "Default")
      (node (ref "IC2") (pin "10") (pinfunction "W/RDYA_10") (pintype "output"))
    )
    (net (code "146") (name "unconnected-(IC2-W{slash}RDYB-Pad30)") (class "Default")
      (node (ref "IC2") (pin "30") (pinfunction "W/RDYB_30") (pintype "output"))
    )
    (net (code "147") (name "unconnected-(IC3-P10-Pad27)") (class "Default")
      (node (ref "IC3") (pin "27") (pinfunction "P10_27") (pintype "bidirectional"))
    )
    (net (code "148") (name "unconnected-(IC3-P11-Pad28)") (class "Default")
      (node (ref "IC3") (pin "28") (pinfunction "P11_28") (pintype "bidirectional"))
    )
    (net (code "149") (name "unconnected-(IC3-P12-Pad29)") (class "Default")
      (node (ref "IC3") (pin "29") (pinfunction "P12_29") (pintype "bidirectional"))
    )
    (net (code "150") (name "unconnected-(IC3-P13-Pad30)") (class "Default")
      (node (ref "IC3") (pin "30") (pinfunction "P13_30") (pintype "bidirectional"))
    )
    (net (code "151") (name "unconnected-(IC3-P14-Pad31)") (class "Default")
      (node (ref "IC3") (pin "31") (pinfunction "P14_31") (pintype "bidirectional"))
    )
    (net (code "152") (name "unconnected-(IC3-P15-Pad32)") (class "Default")
      (node (ref "IC3") (pin "32") (pinfunction "P15_32") (pintype "bidirectional"))
    )
    (net (code "153") (name "unconnected-(IC3-P16-Pad33)") (class "Default")
      (node (ref "IC3") (pin "33") (pinfunction "P16_33") (pintype "bidirectional"))
    )
    (net (code "154") (name "unconnected-(IC3-P17-Pad34)") (class "Default")
      (node (ref "IC3") (pin "34") (pinfunction "P17_34") (pintype "bidirectional"))
    )
    (net (code "155") (name "unconnected-(IC3-P20-Pad21)") (class "Default")
      (node (ref "IC3") (pin "21") (pinfunction "P20_21") (pintype "bidirectional"))
    )
    (net (code "156") (name "unconnected-(IC3-P21-Pad22)") (class "Default")
      (node (ref "IC3") (pin "22") (pinfunction "P21_22") (pintype "bidirectional"))
    )
    (net (code "157") (name "unconnected-(IC3-P25{slash}~{IBF}-Pad36)") (class "Default")
      (node (ref "IC3") (pin "36") (pinfunction "P25/~{IBF}_36") (pintype "bidirectional"))
    )
    (net (code "158") (name "unconnected-(IC3-SYNC-Pad11)") (class "Default")
      (node (ref "IC3") (pin "11") (pinfunction "SYNC_11") (pintype "output"))
    )
    (net (code "159") (name "unconnected-(IC4A-Y2-Pad6)") (class "Default")
      (node (ref "IC4") (pin "6") (pinfunction "Y2_6") (pintype "output"))
    )
    (net (code "160") (name "unconnected-(IC4A-Y3-Pad7)") (class "Default")
      (node (ref "IC4") (pin "7") (pinfunction "Y3_7") (pintype "output"))
    )
    (net (code "161") (name "unconnected-(IC5C-O-Pad6)") (class "Default")
      (node (ref "IC5") (pin "6") (pinfunction "O_6") (pintype "open_collector"))
    )
    (net (code "162") (name "unconnected-(IC5D-O-Pad8)") (class "Default")
      (node (ref "IC5") (pin "8") (pinfunction "O_8") (pintype "open_collector"))
    )
    (net (code "163") (name "unconnected-(IC5E-O-Pad10)") (class "Default")
      (node (ref "IC5") (pin "10") (pinfunction "O_10") (pintype "open_collector"))
    )
    (net (code "164") (name "unconnected-(IC6-TO1-Pad8)") (class "Default")
      (node (ref "IC6") (pin "8") (pinfunction "TO1_8") (pintype "output"))
    )
    (net (code "165") (name "unconnected-(IC6-TO2-Pad9)") (class "Default")
      (node (ref "IC6") (pin "9") (pinfunction "TO2_9") (pintype "output"))
    )
    (net (code "166") (name "unconnected-(IC9A-B4-Pad15)") (class "Default")
      (node (ref "IC9") (pin "15") (pinfunction "B4_15") (pintype "bidirectional"))
    )
    (net (code "167") (name "unconnected-(IC9A-B5-Pad14)") (class "Default")
      (node (ref "IC9") (pin "14") (pinfunction "B5_14") (pintype "bidirectional"))
    )
    (net (code "168") (name "unconnected-(IC9A-B6-Pad13)") (class "Default")
      (node (ref "IC9") (pin "13") (pinfunction "B6_13") (pintype "bidirectional"))
    )
    (net (code "169") (name "unconnected-(IC10A-B6-Pad13)") (class "Default")
      (node (ref "IC10") (pin "13") (pinfunction "B6_13") (pintype "bidirectional"))
    )
    (net (code "170") (name "unconnected-(IC10A-B7-Pad12)") (class "Default")
      (node (ref "IC10") (pin "12") (pinfunction "B7_12") (pintype "bidirectional"))
    )
    (net (code "171") (name "unconnected-(IC10A-B8-Pad11)") (class "Default")
      (node (ref "IC10") (pin "11") (pinfunction "B8_11") (pintype "bidirectional"))
    )
    (net (code "172") (name "unconnected-(IC12A-QA-Pad3)") (class "Default")
      (node (ref "IC12") (pin "3") (pinfunction "QA_3") (pintype "output"))
    )
    (net (code "173") (name "unconnected-(IC12A-QB-Pad4)") (class "Default")
      (node (ref "IC12") (pin "4") (pinfunction "QB_4") (pintype "output"))
    )
    (net (code "174") (name "unconnected-(IC12A-QC-Pad5)") (class "Default")
      (node (ref "IC12") (pin "5") (pinfunction "QC_5") (pintype "output"))
    )
    (net (code "175") (name "unconnected-(IC12A-QD-Pad6)") (class "Default")
      (node (ref "IC12") (pin "6") (pinfunction "QD_6") (pintype "output"))
    )
    (net (code "176") (name "unconnected-(J1-Pad3)") (class "Default")
      (node (ref "J1") (pin "3") (pinfunction "3_3") (pintype "bidirectional"))
    )
    (net (code "177") (name "unconnected-(SV2-Pad45)") (class "Default")
      (node (ref "SV2") (pin "45") (pinfunction "45_45") (pintype "passive"))
    )
    (net (code "178") (name "unconnected-(SV2-Pad46)") (class "Default")
      (node (ref "SV2") (pin "46") (pinfunction "46_46") (pintype "passive"))
    )
    (net (code "179") (name "unconnected-(SV2-Pad47)") (class "Default")
      (node (ref "SV2") (pin "47") (pinfunction "47_47") (pintype "passive"))
    )
    (net (code "180") (name "unconnected-(SV2-Pad48)") (class "Default")
      (node (ref "SV2") (pin "48") (pinfunction "48_48") (pintype "passive"))
    )
    (net (code "181") (name "unconnected-(SV2-Pad49)") (class "Default")
      (node (ref "SV2") (pin "49") (pinfunction "49_49") (pintype "passive"))
    )
    (net (code "182") (name "unconnected-(SV2-Pad50)") (class "Default")
      (node (ref "SV2") (pin "50") (pinfunction "50_50") (pintype "passive"))
    )
    (net (code "183") (name "unconnected-(SV2-Pad51)") (class "Default")
      (node (ref "SV2") (pin "51") (pinfunction "51_51") (pintype "passive"))
    )
    (net (code "184") (name "unconnected-(SV2-Pad52)") (class "Default")
      (node (ref "SV2") (pin "52") (pinfunction "52_52") (pintype "passive"))
    )
    (net (code "185") (name "unconnected-(SV2-Pad53)") (class "Default")
      (node (ref "SV2") (pin "53") (pinfunction "53_53") (pintype "passive"))
    )
    (net (code "186") (name "unconnected-(SV2-Pad54)") (class "Default")
      (node (ref "SV2") (pin "54") (pinfunction "54_54") (pintype "passive"))
    )
    (net (code "187") (name "unconnected-(SV2-Pad55)") (class "Default")
      (node (ref "SV2") (pin "55") (pinfunction "55_55") (pintype "passive"))
    )
    (net (code "188") (name "unconnected-(SV2-Pad56)") (class "Default")
      (node (ref "SV2") (pin "56") (pinfunction "56_56") (pintype "passive"))
    )
    (net (code "189") (name "unconnected-(SV2-Pad64)") (class "Default")
      (node (ref "SV2") (pin "64") (pinfunction "64_64") (pintype "passive"))
    )
    (net (code "190") (name "unconnected-(X1-Pad1)") (class "Default")
      (node (ref "X1") (pin "1") (pinfunction "1_1") (pintype "passive"))
    )
    (net (code "191") (name "unconnected-(X1-Pad4)") (class "Default")
      (node (ref "X1") (pin "4") (pinfunction "4_4") (pintype "passive"))
    )
    (net (code "192") (name "unconnected-(X1-Pad6)") (class "Default")
      (node (ref "X1") (pin "6") (pinfunction "6_6") (pintype "passive"))
    )
    (net (code "193") (name "unconnected-(X1-Pad9)") (class "Default")
      (node (ref "X1") (pin "9") (pinfunction "9_9") (pintype "passive"))
    )
    (net (code "194") (name "unconnected-(X3-Pad1)") (class "Default")
      (node (ref "X3") (pin "1") (pinfunction "1_1") (pintype "passive"))
    )
    (net (code "195") (name "unconnected-(X3-Pad4)") (class "Default")
      (node (ref "X3") (pin "4") (pinfunction "4_4") (pintype "passive"))
    )
    (net (code "196") (name "unconnected-(X3-Pad6)") (class "Default")
      (node (ref "X3") (pin "6") (pinfunction "6_6") (pintype "passive"))
    )
    (net (code "197") (name "unconnected-(X3-Pad9)") (class "Default")
      (node (ref "X3") (pin "9") (pinfunction "9_9") (pintype "passive"))
    )
  )
)
